# EEM_PWR_MOD_AC.net
KiCad netlist of a schematic drawn in Altium Designer
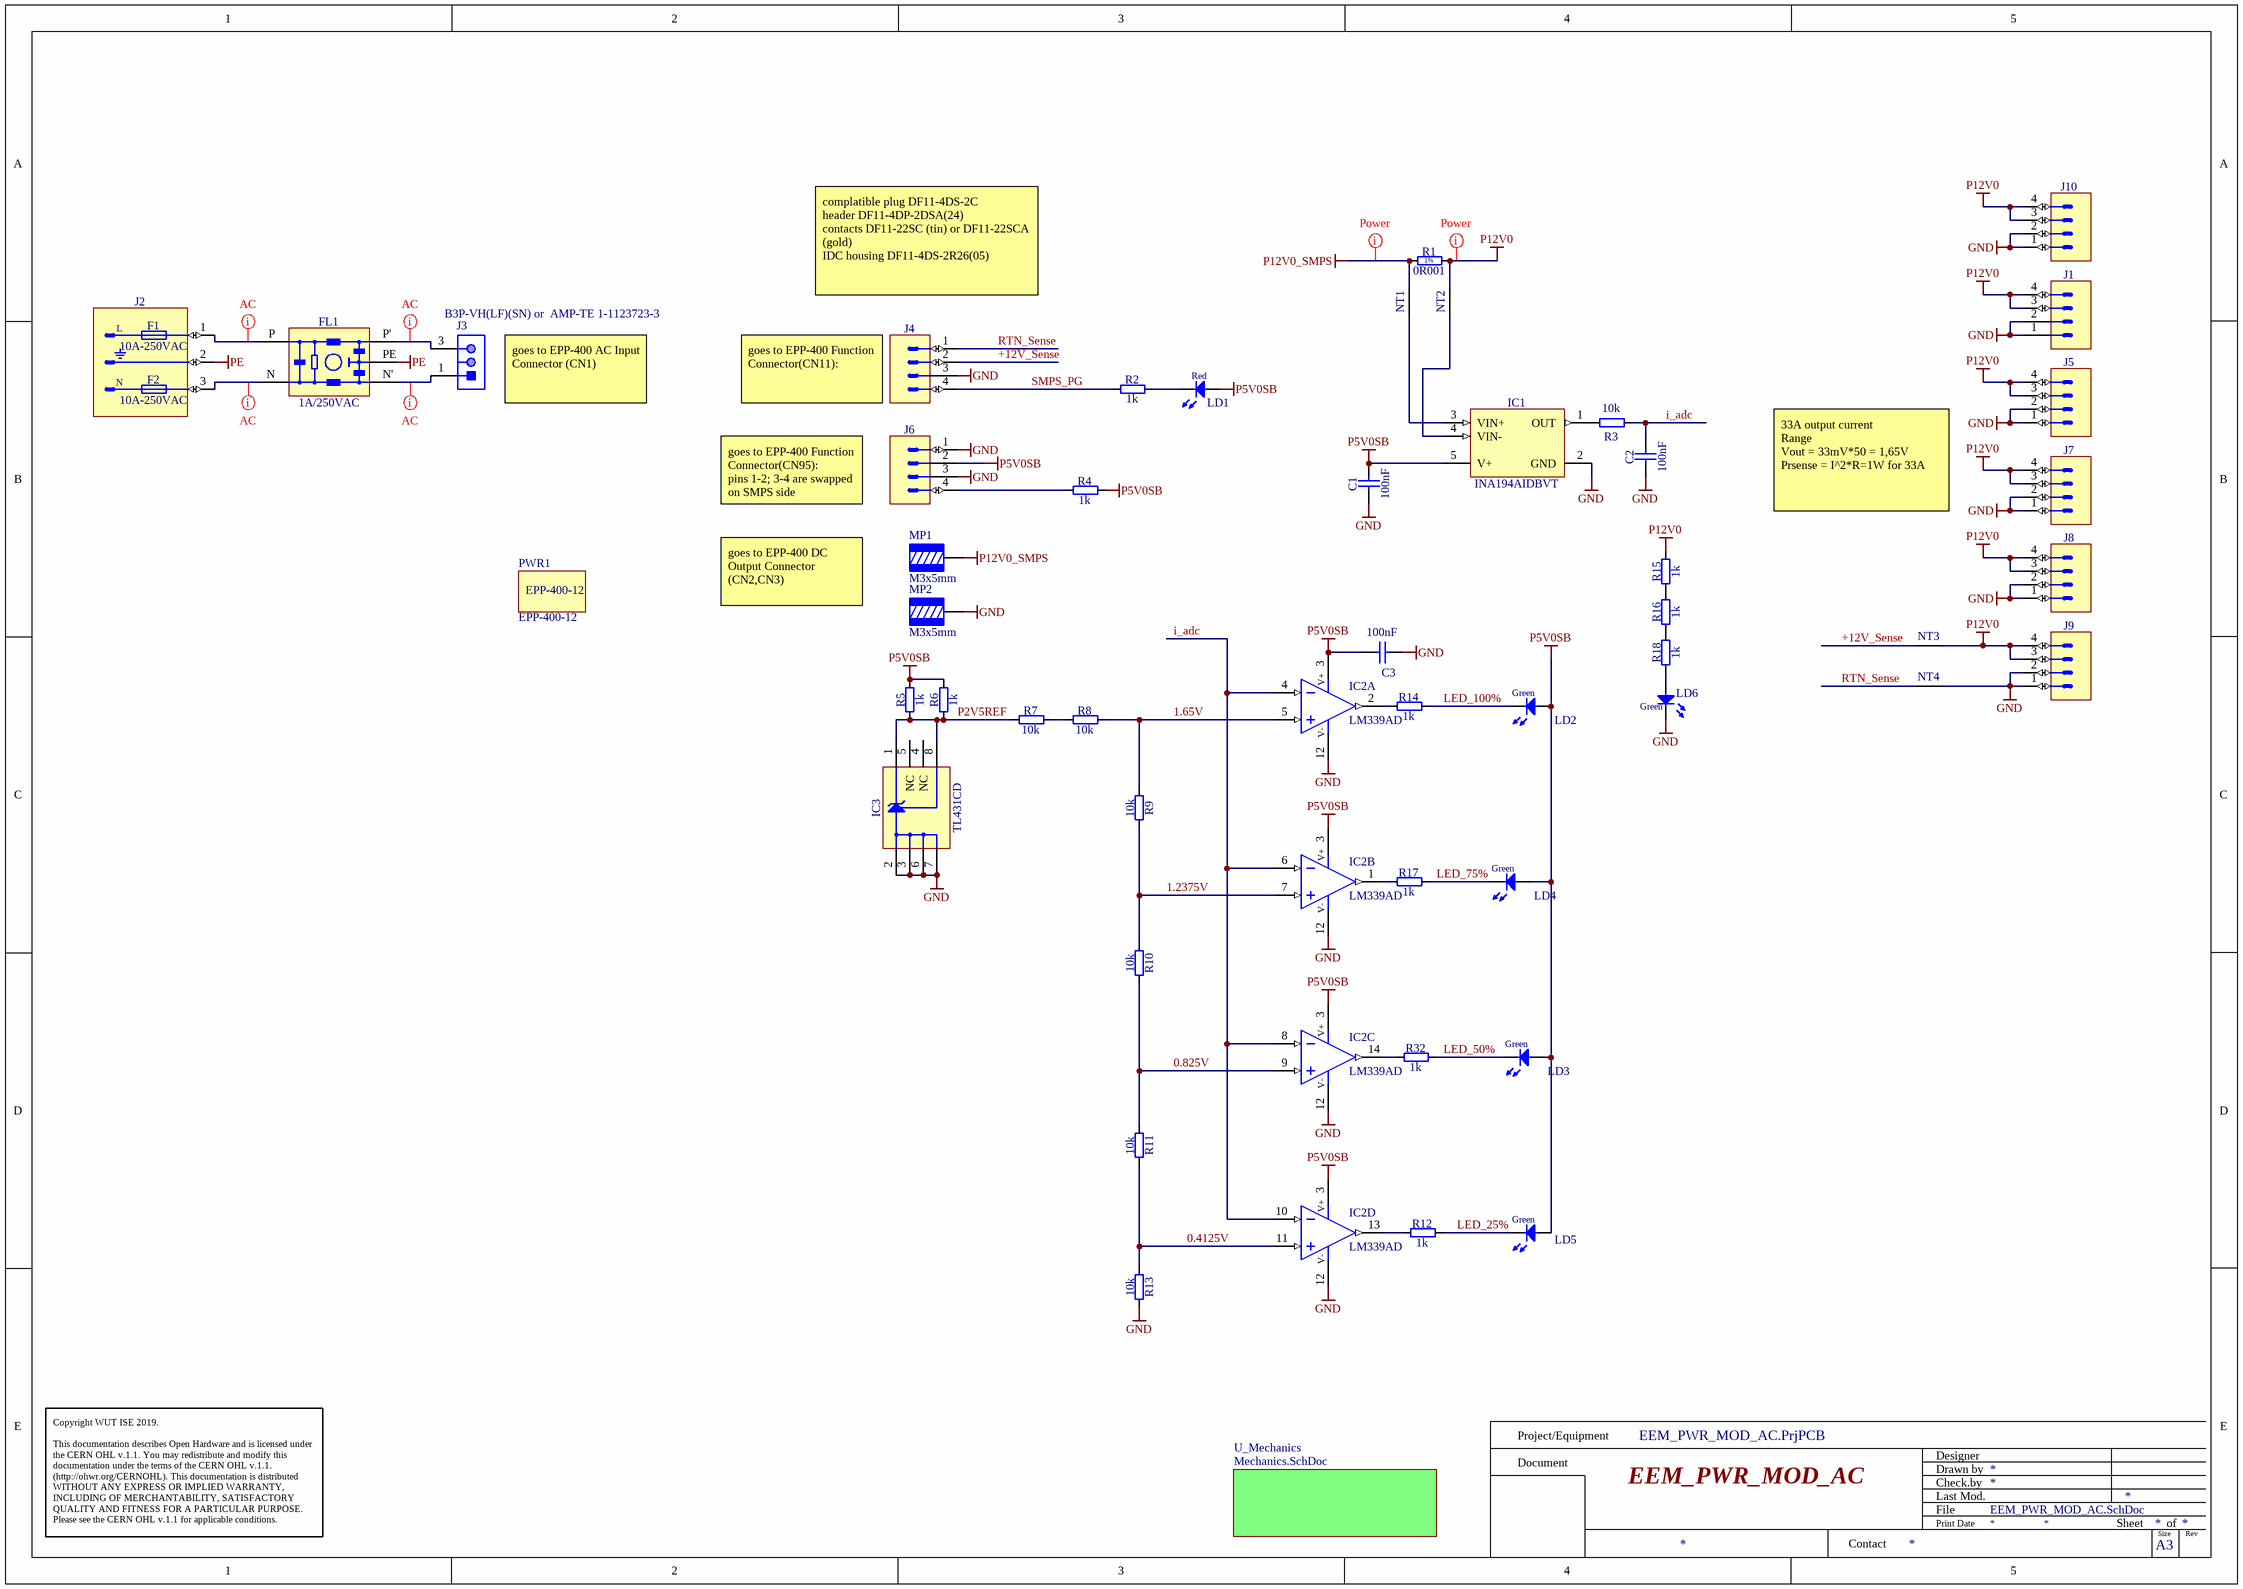
[diagram p0: EEM_PWR_MOD_AC.SchDoc]

(export (version "E")
  (design (tool "Eeschema 10.0.6"))
  (components
    (comp (ref "C1")
      (value "100nF")
      (footprint "CAPC1005X55N")
      (description "Non-polarised capacitor")
      (fields
        (field (name "PART NUMBER") "CC0402_100NF_25V_10%_X7R_YUDEN_TMK105B7104KVHF")
        (field (name "VOLTAGE") "25V")
        (field (name "AUTHOR") "CERN DEM JLC")
      )
      (libsource (lib "Capacitors") (part "Capacitor - non polarized"))
    )
    (comp (ref "C2")
      (value "100nF")
      (footprint "CAPC1005X55N")
      (description "Non-polarised capacitor")
      (fields
        (field (name "PART NUMBER") "CC0402_100NF_25V_10%_X7R_YUDEN_TMK105B7104KVHF")
        (field (name "VOLTAGE") "25V")
        (field (name "AUTHOR") "CERN DEM JLC")
      )
      (libsource (lib "Capacitors") (part "Capacitor - non polarized"))
    )
    (comp (ref "C3")
      (value "100nF")
      (footprint "CAPC1005X55N")
      (description "Non-polarised capacitor")
      (fields
        (field (name "PART NUMBER") "CC0402_100NF_25V_10%_X7R_YUDEN_TMK105B7104KVHF")
        (field (name "VOLTAGE") "25V")
        (field (name "AUTHOR") "CERN DEM JLC")
      )
      (libsource (lib "Capacitors") (part "Capacitor - non polarized"))
    )
    (comp (ref "F1")
      (value "10A-250VAC")
      (footprint "FUSE_5X20_GLASS_v")
      (description "Fuse")
      (fields
        (field (name "PART NUMBER") "FUSE_SCHURTER_0034.3127_v")
        (field (name "MANUFACTURER") "SCHURTER")
        (field (name "AUTHOR") "CERN DEM JLC")
      )
      (libsource (lib "Eletro-mechanical") (part "Fuse No Pin"))
    )
    (comp (ref "F2")
      (value "10A-250VAC")
      (footprint "FUSE_5X20_GLASS_v")
      (description "Fuse")
      (fields
        (field (name "PART NUMBER") "FUSE_SCHURTER_0034.3127_v")
        (field (name "MANUFACTURER") "SCHURTER")
        (field (name "AUTHOR") "CERN DEM JLC")
      )
      (libsource (lib "Eletro-mechanical") (part "Fuse No Pin"))
    )
    (comp (ref "FL1")
      (value "1A/250VAC")
      (footprint "FIL_SCHAFFNER_FN 406")
      (description "0.6 to 8.4A 230VAC Single Phase Ultra Compact EMC Filter")
      (fields
        (field (name "PART NUMBER") "FIL_SCHAFFNER_FN406-3-02")
        (field (name "MANUFACTURER") "SCHAFFNER")
        (field (name "AUTHOR") "CERN DEM JLC")
      )
      (libsource (lib "Inductors & Transformers") (part "FIL_SCHAFFNER_FN 406"))
    )
    (comp (ref "IC1")
      (value "INA194AIDBVT")
      (footprint "SOT95P280X145-5N")
      (description "Current Shunt Monitor -16V to +80V Common-Mode Range")
      (fields (field (name "MANUFACTURER") "TEXAS INSTRUMENTS") (field (name "AUTHOR") "CERN DEM JLC"))
      (libsource (lib "ICs And Semiconductors") (part "INA194"))
    )
    (comp (ref "IC2")
      (value "LM339AD")
      (footprint "SOIC127P600X175-14N")
      (description "Quad Operational Amplifier")
      (fields (field (name "MANUFACTURER") "TEXAS INSTRUMENTS") (field (name "AUTHOR") "CERN DEM JLC"))
      (libsource (lib "ICs And Semiconductors") (part "Operational Amplifier x4 Type2"))
    )
    (comp (ref "IC3")
      (value "TL431CD")
      (footprint "SOIC127P600X175-8N")
      (description "Precision Programmable Reference")
      (fields (field (name "MANUFACTURER") "TEXAS INSTRUMENTS") (field (name "AUTHOR") "CERN DEM JLC"))
      (libsource (lib "ICs And Semiconductors") (part "TL431xD"))
    )
    (comp (ref "J1")
      (value "Mini-Fit Jr.™")
      (footprint "MOLEX_39-30-0040")
      (description "Connector 4 Male")
      (fields
        (field (name "PART NUMBER") "MOLEX_39-30-0040")
        (field (name "MANUFACTURER") "MOLEX")
        (field (name "AUTHOR") "CERN DEM JLC")
      )
      (libsource (lib "Connectors") (part "Connector 4 Male"))
    )
    (comp (ref "J2")
      (value "IEC")
      (footprint "SCHURTER_GSF1.2202.31")
      (description "Connector 3 Male 2P+ 2 Fuse Holder")
      (fields
        (field (name "PART NUMBER") "SCHURTER_GSF1.2201.31")
        (field (name "MANUFACTURER") "SCHURTER")
        (field (name "AUTHOR") "CERN DEM JMW")
      )
      (libsource (lib "Connectors") (part "Connector 3 Male 2P+T+2FUSH"))
    )
    (comp (ref "J3")
      (value "B3P-VH(LF)(SN) or  AMP-TE 1-1123723-3")
      (footprint "JST-B3P-VH(LF)(SN)-3_V")
      (fields (field (name "MANUFACTURER PART NUMBER") "B3P-VH(LF)(SN)"))
      (libsource (lib "Altium Content Vault") (part "CN-1P-M-R3"))
    )
    (comp (ref "J4")
      (value "Header 4")
      (footprint "HIROSE_DF11-4DP-2DSA")
      (description "Connector 4 Male")
      (fields
        (field (name "PART NUMBER") "HIROSE_DF11-4DP-2DSA")
        (field (name "MANUFACTURER") "HIROSE (HRS)")
        (field (name "AUTHOR") "GK")
      )
      (libsource (lib "Connectors") (part "CON_4_HIROSE_DF11-4DP-2DSA"))
    )
    (comp (ref "J5")
      (value "Mini-Fit Jr.™")
      (footprint "MOLEX_39-30-0040")
      (description "Connector 4 Male")
      (fields
        (field (name "PART NUMBER") "MOLEX_39-30-0040")
        (field (name "MANUFACTURER") "MOLEX")
        (field (name "AUTHOR") "CERN DEM JLC")
      )
      (libsource (lib "Connectors") (part "Connector 4 Male"))
    )
    (comp (ref "J6")
      (value "Header 4")
      (footprint "HIROSE_DF11-4DP-2DSA")
      (description "Connector 4 Male")
      (fields
        (field (name "PART NUMBER") "HIROSE_DF11-4DP-2DSA")
        (field (name "MANUFACTURER") "HIROSE (HRS)")
        (field (name "AUTHOR") "GK")
      )
      (libsource (lib "Connectors") (part "CON_4_HIROSE_DF11-4DP-2DSA"))
    )
    (comp (ref "J7")
      (value "Mini-Fit Jr.™")
      (footprint "MOLEX_39-30-0040")
      (description "Connector 4 Male")
      (fields
        (field (name "PART NUMBER") "MOLEX_39-30-0040")
        (field (name "MANUFACTURER") "MOLEX")
        (field (name "AUTHOR") "CERN DEM JLC")
      )
      (libsource (lib "Connectors") (part "Connector 4 Male"))
    )
    (comp (ref "J8")
      (value "Mini-Fit Jr.™")
      (footprint "MOLEX_39-30-0040")
      (description "Connector 4 Male")
      (fields
        (field (name "PART NUMBER") "MOLEX_39-30-0040")
        (field (name "MANUFACTURER") "MOLEX")
        (field (name "AUTHOR") "CERN DEM JLC")
      )
      (libsource (lib "Connectors") (part "Connector 4 Male"))
    )
    (comp (ref "J9")
      (value "Mini-Fit Jr.™")
      (footprint "MOLEX_39-30-0040")
      (description "Connector 4 Male")
      (fields
        (field (name "PART NUMBER") "MOLEX_39-30-0040")
        (field (name "MANUFACTURER") "MOLEX")
        (field (name "AUTHOR") "CERN DEM JLC")
      )
      (libsource (lib "Connectors") (part "Connector 4 Male"))
    )
    (comp (ref "J10")
      (value "Mini-Fit Jr.™")
      (footprint "MOLEX_39-30-0040")
      (description "Connector 4 Male")
      (fields
        (field (name "PART NUMBER") "MOLEX_39-30-0040")
        (field (name "MANUFACTURER") "MOLEX")
        (field (name "AUTHOR") "CERN DEM JLC")
      )
      (libsource (lib "Connectors") (part "Connector 4 Male"))
    )
    (comp (ref "LD1")
      (value "Red")
      (footprint "LED_AVAGO_HSMC-C120")
      (description "LED Red 1C 2A")
      (fields
        (field (name "PART NUMBER") "LED_AVAGO_HSMC-C120")
        (field (name "MANUFACTURER") "AVAGO TECHNOLOGIES")
        (field (name "AUTHOR") "CERN DEM JMW")
      )
      (libsource (lib "ICs And Semiconductors") (part "LED Red 1C 2A"))
    )
    (comp (ref "LD2")
      (value "Green")
      (footprint "LED_AVAGO_HSME-C120")
      (description "LED Green 1C 2A")
      (fields
        (field (name "PART NUMBER") "LED_AVAGO_HSME-C120")
        (field (name "MANUFACTURER") "AVAGO TECHNOLOGIES")
        (field (name "AUTHOR") "CERN DEM JMW")
      )
      (libsource (lib "ICs And Semiconductors") (part "LED Green 1C 2A"))
    )
    (comp (ref "LD3")
      (value "Green")
      (footprint "LED_AVAGO_HSME-C120")
      (description "LED Green 1C 2A")
      (fields
        (field (name "PART NUMBER") "LED_AVAGO_HSME-C120")
        (field (name "MANUFACTURER") "AVAGO TECHNOLOGIES")
        (field (name "AUTHOR") "CERN DEM JMW")
      )
      (libsource (lib "ICs And Semiconductors") (part "LED Green 1C 2A"))
    )
    (comp (ref "LD4")
      (value "Green")
      (footprint "LED_AVAGO_HSME-C120")
      (description "LED Green 1C 2A")
      (fields
        (field (name "PART NUMBER") "LED_AVAGO_HSME-C120")
        (field (name "MANUFACTURER") "AVAGO TECHNOLOGIES")
        (field (name "AUTHOR") "CERN DEM JMW")
      )
      (libsource (lib "ICs And Semiconductors") (part "LED Green 1C 2A"))
    )
    (comp (ref "LD5")
      (value "Green")
      (footprint "LED_AVAGO_HSME-C120")
      (description "LED Green 1C 2A")
      (fields
        (field (name "PART NUMBER") "LED_AVAGO_HSME-C120")
        (field (name "MANUFACTURER") "AVAGO TECHNOLOGIES")
        (field (name "AUTHOR") "CERN DEM JMW")
      )
      (libsource (lib "ICs And Semiconductors") (part "LED Green 1C 2A"))
    )
    (comp (ref "LD6")
      (value "Green")
      (footprint "LED_AVAGO_HSME-C120")
      (description "LED Green 1C 2A")
      (fields
        (field (name "PART NUMBER") "LED_AVAGO_HSME-C120")
        (field (name "MANUFACTURER") "AVAGO TECHNOLOGIES")
        (field (name "AUTHOR") "CERN DEM JMW")
      )
      (libsource (lib "ICs And Semiconductors") (part "LED Green 1C 2A"))
    )
    (comp (ref "MP1")
      (value "M3x5mm")
      (footprint "7461057_for chemical surfaces")
      (description "WP-BUTR Press-Fit with Internal thread, two rows, 7x7mm, 6 pins, M3x5mm, 100A")
      (fields
        (field (name "MANUFACTURER PART NUMBER") "7461057")
        (field (name "PUBLISHER") "Wurth Elektronik")
      )
      (libsource (lib "7460307_Altium_WP-BUTR_rev19a") (part "7461057"))
    )
    (comp (ref "MP2")
      (value "M3x5mm")
      (footprint "7461057_for chemical surfaces")
      (description "WP-BUTR Press-Fit with Internal thread, two rows, 7x7mm, 6 pins, M3x5mm, 100A")
      (fields
        (field (name "MANUFACTURER PART NUMBER") "7461057")
        (field (name "PUBLISHER") "Wurth Elektronik")
      )
      (libsource (lib "7460307_Altium_WP-BUTR_rev19a") (part "7461057"))
    )
    (comp (ref "NT1")
      (value "Net Tie")
      (footprint "Net Tie")
      (fields (field (name "AUTHOR") "CERN DEM JLC"))
      (libsource (lib "Eletro-mechanical") (part "Net Tie"))
    )
    (comp (ref "NT2")
      (value "Net Tie")
      (footprint "Net Tie")
      (fields (field (name "AUTHOR") "CERN DEM JLC"))
      (libsource (lib "Eletro-mechanical") (part "Net Tie"))
    )
    (comp (ref "NT3")
      (value "Net Tie")
      (footprint "Net Tie")
      (fields (field (name "AUTHOR") "CERN DEM JLC"))
      (libsource (lib "Eletro-mechanical") (part "Net Tie"))
    )
    (comp (ref "NT4")
      (value "Net Tie")
      (footprint "Net Tie")
      (fields (field (name "AUTHOR") "CERN DEM JLC"))
      (libsource (lib "Eletro-mechanical") (part "Net Tie"))
    )
    (comp (ref "PWR1")
      (value "EPP-400-12")
      (footprint "EPP-400-12")
      (description "Switching Power Supplies 399.6W 12V 33.3A 3X5 open frame W/PFC")
      (libsource (lib "Integrated_Library_LOADER") (part "EPP-400-12"))
    )
    (comp (ref "R1")
      (value "0R001")
      (footprint "RESM11670X254N")
      (description "Resistor - 1%")
      (fields
        (field (name "PART NUMBER") "R4527_0R001_1%_2W_75PPM")
        (field (name "POWER") "2W")
        (field (name "AUTHOR") "CERN DEM JLC")
      )
      (libsource (lib "") (part "Resistor - 1%_1"))
    )
    (comp (ref "R2")
      (value "1k")
      (footprint "RESC1608X55N")
      (description "Resistor - 1%")
      (fields
        (field (name "PART NUMBER") "R0603_1K_1%_0.1W_100PPM")
        (field (name "POWER") "0.1W")
        (field (name "AUTHOR") "CERN DEM JLC")
      )
      (libsource (lib "Resistors") (part "Resistor - 1%"))
    )
    (comp (ref "R3")
      (value "10k")
      (footprint "RESC1608X55N")
      (description "Resistor - 1%")
      (fields
        (field (name "PART NUMBER") "R0603_10K_1%_0.1W_100PPM")
        (field (name "POWER") "0.1W")
        (field (name "AUTHOR") "CERN DEM JLC")
      )
      (libsource (lib "Resistors") (part "Resistor - 1%"))
    )
    (comp (ref "R4")
      (value "1k")
      (footprint "RESC1608X55N")
      (description "Resistor - 1%")
      (fields
        (field (name "PART NUMBER") "R0603_1K_1%_0.1W_100PPM")
        (field (name "POWER") "0.1W")
        (field (name "AUTHOR") "CERN DEM JLC")
      )
      (libsource (lib "Resistors") (part "Resistor - 1%"))
    )
    (comp (ref "R5")
      (value "1k")
      (footprint "RESC1608X55N")
      (description "Resistor - 1%")
      (fields
        (field (name "PART NUMBER") "R0603_1K_1%_0.1W_100PPM")
        (field (name "POWER") "0.1W")
        (field (name "AUTHOR") "CERN DEM JLC")
      )
      (libsource (lib "Resistors") (part "Resistor - 1%"))
    )
    (comp (ref "R6")
      (value "1k")
      (footprint "RESC1608X55N")
      (description "Resistor - 1%")
      (fields
        (field (name "PART NUMBER") "R0603_1K_1%_0.1W_100PPM")
        (field (name "POWER") "0.1W")
        (field (name "AUTHOR") "CERN DEM JLC")
      )
      (libsource (lib "Resistors") (part "Resistor - 1%"))
    )
    (comp (ref "R7")
      (value "10k")
      (footprint "RESC1608X55N")
      (description "Resistor - 1%")
      (fields
        (field (name "PART NUMBER") "R0603_10K_1%_0.1W_100PPM")
        (field (name "POWER") "0.1W")
        (field (name "AUTHOR") "CERN DEM JLC")
      )
      (libsource (lib "Resistors") (part "Resistor - 1%"))
    )
    (comp (ref "R8")
      (value "10k")
      (footprint "RESC1608X55N")
      (description "Resistor - 1%")
      (fields
        (field (name "PART NUMBER") "R0603_10K_1%_0.1W_100PPM")
        (field (name "POWER") "0.1W")
        (field (name "AUTHOR") "CERN DEM JLC")
      )
      (libsource (lib "Resistors") (part "Resistor - 1%"))
    )
    (comp (ref "R9")
      (value "10k")
      (footprint "RESC1608X55N")
      (description "Resistor - 1%")
      (fields
        (field (name "PART NUMBER") "R0603_10K_1%_0.1W_100PPM")
        (field (name "POWER") "0.1W")
        (field (name "AUTHOR") "CERN DEM JLC")
      )
      (libsource (lib "Resistors") (part "Resistor - 1%"))
    )
    (comp (ref "R10")
      (value "10k")
      (footprint "RESC1608X55N")
      (description "Resistor - 1%")
      (fields
        (field (name "PART NUMBER") "R0603_10K_1%_0.1W_100PPM")
        (field (name "POWER") "0.1W")
        (field (name "AUTHOR") "CERN DEM JLC")
      )
      (libsource (lib "Resistors") (part "Resistor - 1%"))
    )
    (comp (ref "R11")
      (value "10k")
      (footprint "RESC1608X55N")
      (description "Resistor - 1%")
      (fields
        (field (name "PART NUMBER") "R0603_10K_1%_0.1W_100PPM")
        (field (name "POWER") "0.1W")
        (field (name "AUTHOR") "CERN DEM JLC")
      )
      (libsource (lib "Resistors") (part "Resistor - 1%"))
    )
    (comp (ref "R12")
      (value "1k")
      (footprint "RESC1608X55N")
      (description "Resistor - 1%")
      (fields
        (field (name "PART NUMBER") "R0603_1K_1%_0.1W_100PPM")
        (field (name "POWER") "0.1W")
        (field (name "AUTHOR") "CERN DEM JLC")
      )
      (libsource (lib "Resistors") (part "Resistor - 1%"))
    )
    (comp (ref "R13")
      (value "10k")
      (footprint "RESC1608X55N")
      (description "Resistor - 1%")
      (fields
        (field (name "PART NUMBER") "R0603_10K_1%_0.1W_100PPM")
        (field (name "POWER") "0.1W")
        (field (name "AUTHOR") "CERN DEM JLC")
      )
      (libsource (lib "Resistors") (part "Resistor - 1%"))
    )
    (comp (ref "R14")
      (value "1k")
      (footprint "RESC1608X55N")
      (description "Resistor - 1%")
      (fields
        (field (name "PART NUMBER") "R0603_1K_1%_0.1W_100PPM")
        (field (name "POWER") "0.1W")
        (field (name "AUTHOR") "CERN DEM JLC")
      )
      (libsource (lib "Resistors") (part "Resistor - 1%"))
    )
    (comp (ref "R15")
      (value "1k")
      (footprint "RESC1608X55N")
      (description "Resistor - 1%")
      (fields
        (field (name "PART NUMBER") "R0603_1K_1%_0.1W_100PPM")
        (field (name "POWER") "0.1W")
        (field (name "AUTHOR") "CERN DEM JLC")
      )
      (libsource (lib "Resistors") (part "Resistor - 1%"))
    )
    (comp (ref "R16")
      (value "1k")
      (footprint "RESC1608X55N")
      (description "Resistor - 1%")
      (fields
        (field (name "PART NUMBER") "R0603_1K_1%_0.1W_100PPM")
        (field (name "POWER") "0.1W")
        (field (name "AUTHOR") "CERN DEM JLC")
      )
      (libsource (lib "Resistors") (part "Resistor - 1%"))
    )
    (comp (ref "R17")
      (value "1k")
      (footprint "RESC1608X55N")
      (description "Resistor - 1%")
      (fields
        (field (name "PART NUMBER") "R0603_1K_1%_0.1W_100PPM")
        (field (name "POWER") "0.1W")
        (field (name "AUTHOR") "CERN DEM JLC")
      )
      (libsource (lib "Resistors") (part "Resistor - 1%"))
    )
    (comp (ref "R18")
      (value "1k")
      (footprint "RESC1608X55N")
      (description "Resistor - 1%")
      (fields
        (field (name "PART NUMBER") "R0603_1K_1%_0.1W_100PPM")
        (field (name "POWER") "0.1W")
        (field (name "AUTHOR") "CERN DEM JLC")
      )
      (libsource (lib "Resistors") (part "Resistor - 1%"))
    )
    (comp (ref "R32")
      (value "1k")
      (footprint "RESC1608X55N")
      (description "Resistor - 1%")
      (fields
        (field (name "PART NUMBER") "R0603_1K_1%_0.1W_100PPM")
        (field (name "POWER") "0.1W")
        (field (name "AUTHOR") "CERN DEM JLC")
      )
      (libsource (lib "Resistors") (part "Resistor - 1%"))
    )
  )
  (nets
    (net (code "1") (name "/+12V_Sense") (class "Default")
      (node (ref "J4") (pin "2") (pinfunction "2_2") (pintype "bidirectional"))
      (node (ref "NT3") (pin "1") (pinfunction "1_1") (pintype "bidirectional"))
    )
    (net (code "2") (name "/0.825V") (class "Default")
      (node (ref "IC2") (pin "9") (pinfunction "IN+_9") (pintype "input"))
      (node (ref "R10") (pin "2") (pinfunction "2_2") (pintype "passive"))
      (node (ref "R11") (pin "1") (pinfunction "1_1") (pintype "passive"))
    )
    (net (code "3") (name "/0.4125V") (class "Default")
      (node (ref "IC2") (pin "11") (pinfunction "IN+_11") (pintype "input"))
      (node (ref "R11") (pin "2") (pinfunction "2_2") (pintype "passive"))
      (node (ref "R13") (pin "1") (pinfunction "1_1") (pintype "passive"))
    )
    (net (code "4") (name "/1.65V") (class "Default")
      (node (ref "IC2") (pin "5") (pinfunction "IN+_5") (pintype "input"))
      (node (ref "R8") (pin "2") (pinfunction "2_2") (pintype "passive"))
      (node (ref "R9") (pin "1") (pinfunction "1_1") (pintype "passive"))
    )
    (net (code "5") (name "/1.2375V") (class "Default")
      (node (ref "IC2") (pin "7") (pinfunction "IN+_7") (pintype "input"))
      (node (ref "R10") (pin "1") (pinfunction "1_1") (pintype "passive"))
      (node (ref "R9") (pin "2") (pinfunction "2_2") (pintype "passive"))
    )
    (net (code "6") (name "/LED_25%") (class "Default")
      (node (ref "LD5") (pin "1") (pinfunction "C_1") (pintype "passive"))
      (node (ref "R12") (pin "2") (pinfunction "2_2") (pintype "passive"))
    )
    (net (code "7") (name "/LED_50%") (class "Default")
      (node (ref "LD3") (pin "1") (pinfunction "C_1") (pintype "passive"))
      (node (ref "R32") (pin "2") (pinfunction "2_2") (pintype "passive"))
    )
    (net (code "8") (name "/LED_75%") (class "Default")
      (node (ref "LD4") (pin "1") (pinfunction "C_1") (pintype "passive"))
      (node (ref "R17") (pin "2") (pinfunction "2_2") (pintype "passive"))
    )
    (net (code "9") (name "/LED_100%") (class "Default")
      (node (ref "LD2") (pin "1") (pinfunction "C_1") (pintype "passive"))
      (node (ref "R14") (pin "2") (pinfunction "2_2") (pintype "passive"))
    )
    (net (code "10") (name "/P2V5REF") (class "Default")
      (node (ref "IC3") (pin "1") (pinfunction "C_1") (pintype "passive"))
      (node (ref "IC3") (pin "8") (pinfunction "REF_8") (pintype "passive"))
      (node (ref "R5") (pin "1") (pinfunction "1_1") (pintype "passive"))
      (node (ref "R6") (pin "1") (pinfunction "1_1") (pintype "passive"))
      (node (ref "R7") (pin "1") (pinfunction "1_1") (pintype "passive"))
    )
    (net (code "11") (name "/RTN_Sense") (class "Default")
      (node (ref "J4") (pin "1") (pinfunction "1_1") (pintype "bidirectional"))
      (node (ref "NT4") (pin "1") (pinfunction "1_1") (pintype "bidirectional"))
    )
    (net (code "12") (name "/SMPS_PG") (class "Default")
      (node (ref "J4") (pin "4") (pinfunction "4_4") (pintype "bidirectional"))
      (node (ref "R2") (pin "1") (pinfunction "1_1") (pintype "passive"))
    )
    (net (code "13") (name "/i_adc") (class "Default")
      (node (ref "C2") (pin "2") (pinfunction "2_2") (pintype "passive"))
      (node (ref "IC2") (pin "10") (pinfunction "IN-_10") (pintype "input"))
      (node (ref "IC2") (pin "4") (pinfunction "IN-_4") (pintype "input"))
      (node (ref "IC2") (pin "6") (pinfunction "IN-_6") (pintype "input"))
      (node (ref "IC2") (pin "8") (pinfunction "IN-_8") (pintype "input"))
      (node (ref "R3") (pin "1") (pinfunction "1_1") (pintype "passive"))
    )
    (net (code "14") (name "GND") (class "Default")
      (node (ref "C1") (pin "1") (pinfunction "1_1") (pintype "passive"))
      (node (ref "C2") (pin "1") (pinfunction "1_1") (pintype "passive"))
      (node (ref "C3") (pin "1") (pinfunction "1_1") (pintype "passive"))
      (node (ref "IC1") (pin "2") (pinfunction "GND_2") (pintype "power_in"))
      (node (ref "IC2") (pin "12") (pinfunction "V-_12") (pintype "power_in"))
      (node (ref "IC3") (pin "2") (pinfunction "A_2") (pintype "passive"))
      (node (ref "IC3") (pin "3") (pinfunction "A_3") (pintype "passive"))
      (node (ref "IC3") (pin "6") (pinfunction "A_6") (pintype "passive"))
      (node (ref "IC3") (pin "7") (pinfunction "A_7") (pintype "passive"))
      (node (ref "J1") (pin "1") (pinfunction "1_1") (pintype "bidirectional"))
      (node (ref "J1") (pin "2") (pinfunction "2_2") (pintype "bidirectional"))
      (node (ref "J10") (pin "1") (pinfunction "1_1") (pintype "bidirectional"))
      (node (ref "J10") (pin "2") (pinfunction "2_2") (pintype "bidirectional"))
      (node (ref "J4") (pin "3") (pinfunction "3_3") (pintype "power_in"))
      (node (ref "J5") (pin "1") (pinfunction "1_1") (pintype "bidirectional"))
      (node (ref "J5") (pin "2") (pinfunction "2_2") (pintype "bidirectional"))
      (node (ref "J6") (pin "1") (pinfunction "1_1") (pintype "bidirectional"))
      (node (ref "J6") (pin "3") (pinfunction "3_3") (pintype "power_in"))
      (node (ref "J7") (pin "1") (pinfunction "1_1") (pintype "bidirectional"))
      (node (ref "J7") (pin "2") (pinfunction "2_2") (pintype "bidirectional"))
      (node (ref "J8") (pin "1") (pinfunction "1_1") (pintype "bidirectional"))
      (node (ref "J8") (pin "2") (pinfunction "2_2") (pintype "bidirectional"))
      (node (ref "J9") (pin "1") (pinfunction "1_1") (pintype "bidirectional"))
      (node (ref "J9") (pin "2") (pinfunction "2_2") (pintype "bidirectional"))
      (node (ref "LD6") (pin "1") (pinfunction "C_1") (pintype "passive"))
      (node (ref "MP2") (pin "1") (pinfunction "1_1") (pintype "passive"))
      (node (ref "NT4") (pin "2") (pinfunction "2_2") (pintype "bidirectional"))
      (node (ref "R13") (pin "2") (pinfunction "2_2") (pintype "passive"))
    )
    (net (code "15") (name "Net-(FL1-PadN')") (class "Default")
      (node (ref "FL1") (pin "N'") (pinfunction "N'_N'") (pintype "power_in"))
      (node (ref "J3") (pin "1") (pinfunction "1_1") (pintype "passive"))
    )
    (net (code "16") (name "Net-(FL1-PadN)") (class "Default")
      (node (ref "FL1") (pin "N") (pinfunction "N_N") (pintype "passive"))
      (node (ref "J2") (pin "3") (pinfunction "3_3") (pintype "bidirectional"))
    )
    (net (code "17") (name "Net-(FL1-PadP')") (class "Default")
      (node (ref "FL1") (pin "P'") (pinfunction "P'_P'") (pintype "passive"))
      (node (ref "J3") (pin "3") (pinfunction "3_3") (pintype "passive"))
    )
    (net (code "18") (name "Net-(FL1-PadP)") (class "Default")
      (node (ref "FL1") (pin "P") (pinfunction "P_P") (pintype "passive"))
      (node (ref "J2") (pin "1") (pinfunction "1_1") (pintype "bidirectional"))
    )
    (net (code "19") (name "Net-(IC1-OUT)") (class "Default")
      (node (ref "IC1") (pin "1") (pinfunction "OUT_1") (pintype "output"))
      (node (ref "R3") (pin "2") (pinfunction "2_2") (pintype "passive"))
    )
    (net (code "20") (name "Net-(IC1-VIN+)") (class "Default")
      (node (ref "IC1") (pin "3") (pinfunction "VIN+_3") (pintype "input"))
      (node (ref "NT1") (pin "1") (pinfunction "1_1") (pintype "bidirectional"))
    )
    (net (code "21") (name "Net-(IC1-VIN-)") (class "Default")
      (node (ref "IC1") (pin "4") (pinfunction "VIN-_4") (pintype "input"))
      (node (ref "NT2") (pin "1") (pinfunction "1_1") (pintype "bidirectional"))
    )
    (net (code "22") (name "Net-(IC2A-OUT)") (class "Default")
      (node (ref "IC2") (pin "2") (pinfunction "OUT_2") (pintype "output"))
      (node (ref "R14") (pin "1") (pinfunction "1_1") (pintype "passive"))
    )
    (net (code "23") (name "Net-(IC2B-OUT)") (class "Default")
      (node (ref "IC2") (pin "1") (pinfunction "OUT_1") (pintype "output"))
      (node (ref "R17") (pin "1") (pinfunction "1_1") (pintype "passive"))
    )
    (net (code "24") (name "Net-(IC2C-OUT)") (class "Default")
      (node (ref "IC2") (pin "14") (pinfunction "OUT_14") (pintype "output"))
      (node (ref "R32") (pin "1") (pinfunction "1_1") (pintype "passive"))
    )
    (net (code "25") (name "Net-(IC2D-OUT)") (class "Default")
      (node (ref "IC2") (pin "13") (pinfunction "OUT_13") (pintype "output"))
      (node (ref "R12") (pin "1") (pinfunction "1_1") (pintype "passive"))
    )
    (net (code "26") (name "Net-(J6-Pad4)") (class "Default")
      (node (ref "J6") (pin "4") (pinfunction "4_4") (pintype "bidirectional"))
      (node (ref "R4") (pin "1") (pinfunction "1_1") (pintype "passive"))
    )
    (net (code "27") (name "Net-(LD1-C)") (class "Default")
      (node (ref "LD1") (pin "1") (pinfunction "C_1") (pintype "passive"))
      (node (ref "R2") (pin "2") (pinfunction "2_2") (pintype "passive"))
    )
    (net (code "28") (name "Net-(LD6-A)") (class "Default")
      (node (ref "LD6") (pin "2") (pinfunction "A_2") (pintype "passive"))
      (node (ref "R18") (pin "1") (pinfunction "1_1") (pintype "passive"))
    )
    (net (code "29") (name "Net-(R7-Pad2)") (class "Default")
      (node (ref "R7") (pin "2") (pinfunction "2_2") (pintype "passive"))
      (node (ref "R8") (pin "1") (pinfunction "1_1") (pintype "passive"))
    )
    (net (code "30") (name "Net-(R15-Pad1)") (class "Default")
      (node (ref "R15") (pin "1") (pinfunction "1_1") (pintype "passive"))
      (node (ref "R16") (pin "2") (pinfunction "2_2") (pintype "passive"))
    )
    (net (code "31") (name "Net-(R16-Pad1)") (class "Default")
      (node (ref "R16") (pin "1") (pinfunction "1_1") (pintype "passive"))
      (node (ref "R18") (pin "2") (pinfunction "2_2") (pintype "passive"))
    )
    (net (code "32") (name "P5V0SB") (class "Default")
      (node (ref "C1") (pin "2") (pinfunction "2_2") (pintype "passive"))
      (node (ref "C3") (pin "2") (pinfunction "2_2") (pintype "passive"))
      (node (ref "IC1") (pin "5") (pinfunction "V+_5") (pintype "power_in"))
      (node (ref "IC2") (pin "3") (pinfunction "V+_3") (pintype "power_in"))
      (node (ref "J6") (pin "2") (pinfunction "2_2") (pintype "bidirectional"))
      (node (ref "LD1") (pin "2") (pinfunction "A_2") (pintype "passive"))
      (node (ref "LD2") (pin "2") (pinfunction "A_2") (pintype "passive"))
      (node (ref "LD3") (pin "2") (pinfunction "A_2") (pintype "passive"))
      (node (ref "LD4") (pin "2") (pinfunction "A_2") (pintype "passive"))
      (node (ref "LD5") (pin "2") (pinfunction "A_2") (pintype "passive"))
      (node (ref "R4") (pin "2") (pinfunction "2_2") (pintype "passive"))
      (node (ref "R5") (pin "2") (pinfunction "2_2") (pintype "passive"))
      (node (ref "R6") (pin "2") (pinfunction "2_2") (pintype "passive"))
    )
    (net (code "33") (name "P12V0") (class "Default")
      (node (ref "J1") (pin "3") (pinfunction "3_3") (pintype "bidirectional"))
      (node (ref "J1") (pin "4") (pinfunction "4_4") (pintype "bidirectional"))
      (node (ref "J10") (pin "3") (pinfunction "3_3") (pintype "bidirectional"))
      (node (ref "J10") (pin "4") (pinfunction "4_4") (pintype "bidirectional"))
      (node (ref "J5") (pin "3") (pinfunction "3_3") (pintype "bidirectional"))
      (node (ref "J5") (pin "4") (pinfunction "4_4") (pintype "bidirectional"))
      (node (ref "J7") (pin "3") (pinfunction "3_3") (pintype "bidirectional"))
      (node (ref "J7") (pin "4") (pinfunction "4_4") (pintype "bidirectional"))
      (node (ref "J8") (pin "3") (pinfunction "3_3") (pintype "bidirectional"))
      (node (ref "J8") (pin "4") (pinfunction "4_4") (pintype "bidirectional"))
      (node (ref "J9") (pin "3") (pinfunction "3_3") (pintype "bidirectional"))
      (node (ref "J9") (pin "4") (pinfunction "4_4") (pintype "bidirectional"))
      (node (ref "NT2") (pin "2") (pinfunction "2_2") (pintype "bidirectional"))
      (node (ref "NT3") (pin "2") (pinfunction "2_2") (pintype "bidirectional"))
      (node (ref "R1") (pin "2") (pinfunction "2_2") (pintype "passive"))
      (node (ref "R15") (pin "2") (pinfunction "2_2") (pintype "passive"))
    )
    (net (code "34") (name "P12V0_SMPS") (class "Default")
      (node (ref "MP1") (pin "1") (pinfunction "1_1") (pintype "passive"))
      (node (ref "NT1") (pin "2") (pinfunction "2_2") (pintype "bidirectional"))
      (node (ref "R1") (pin "1") (pinfunction "1_1") (pintype "passive"))
    )
    (net (code "35") (name "PE") (class "Default")
      (node (ref "FL1") (pin "PE") (pinfunction "PE_PE") (pintype "passive"))
      (node (ref "J2") (pin "2") (pinfunction "2_2") (pintype "bidirectional"))
    )
    (net (code "36") (name "unconnected-(IC3-NC-Pad4)") (class "Default")
      (node (ref "IC3") (pin "4") (pinfunction "NC_4") (pintype "passive"))
    )
    (net (code "37") (name "unconnected-(IC3-NC-Pad5)") (class "Default")
      (node (ref "IC3") (pin "5") (pinfunction "NC_5") (pintype "passive"))
    )
  )
)
